# bottom_schem.net
KiCad netlist of a schematic drawn in Altium Designer
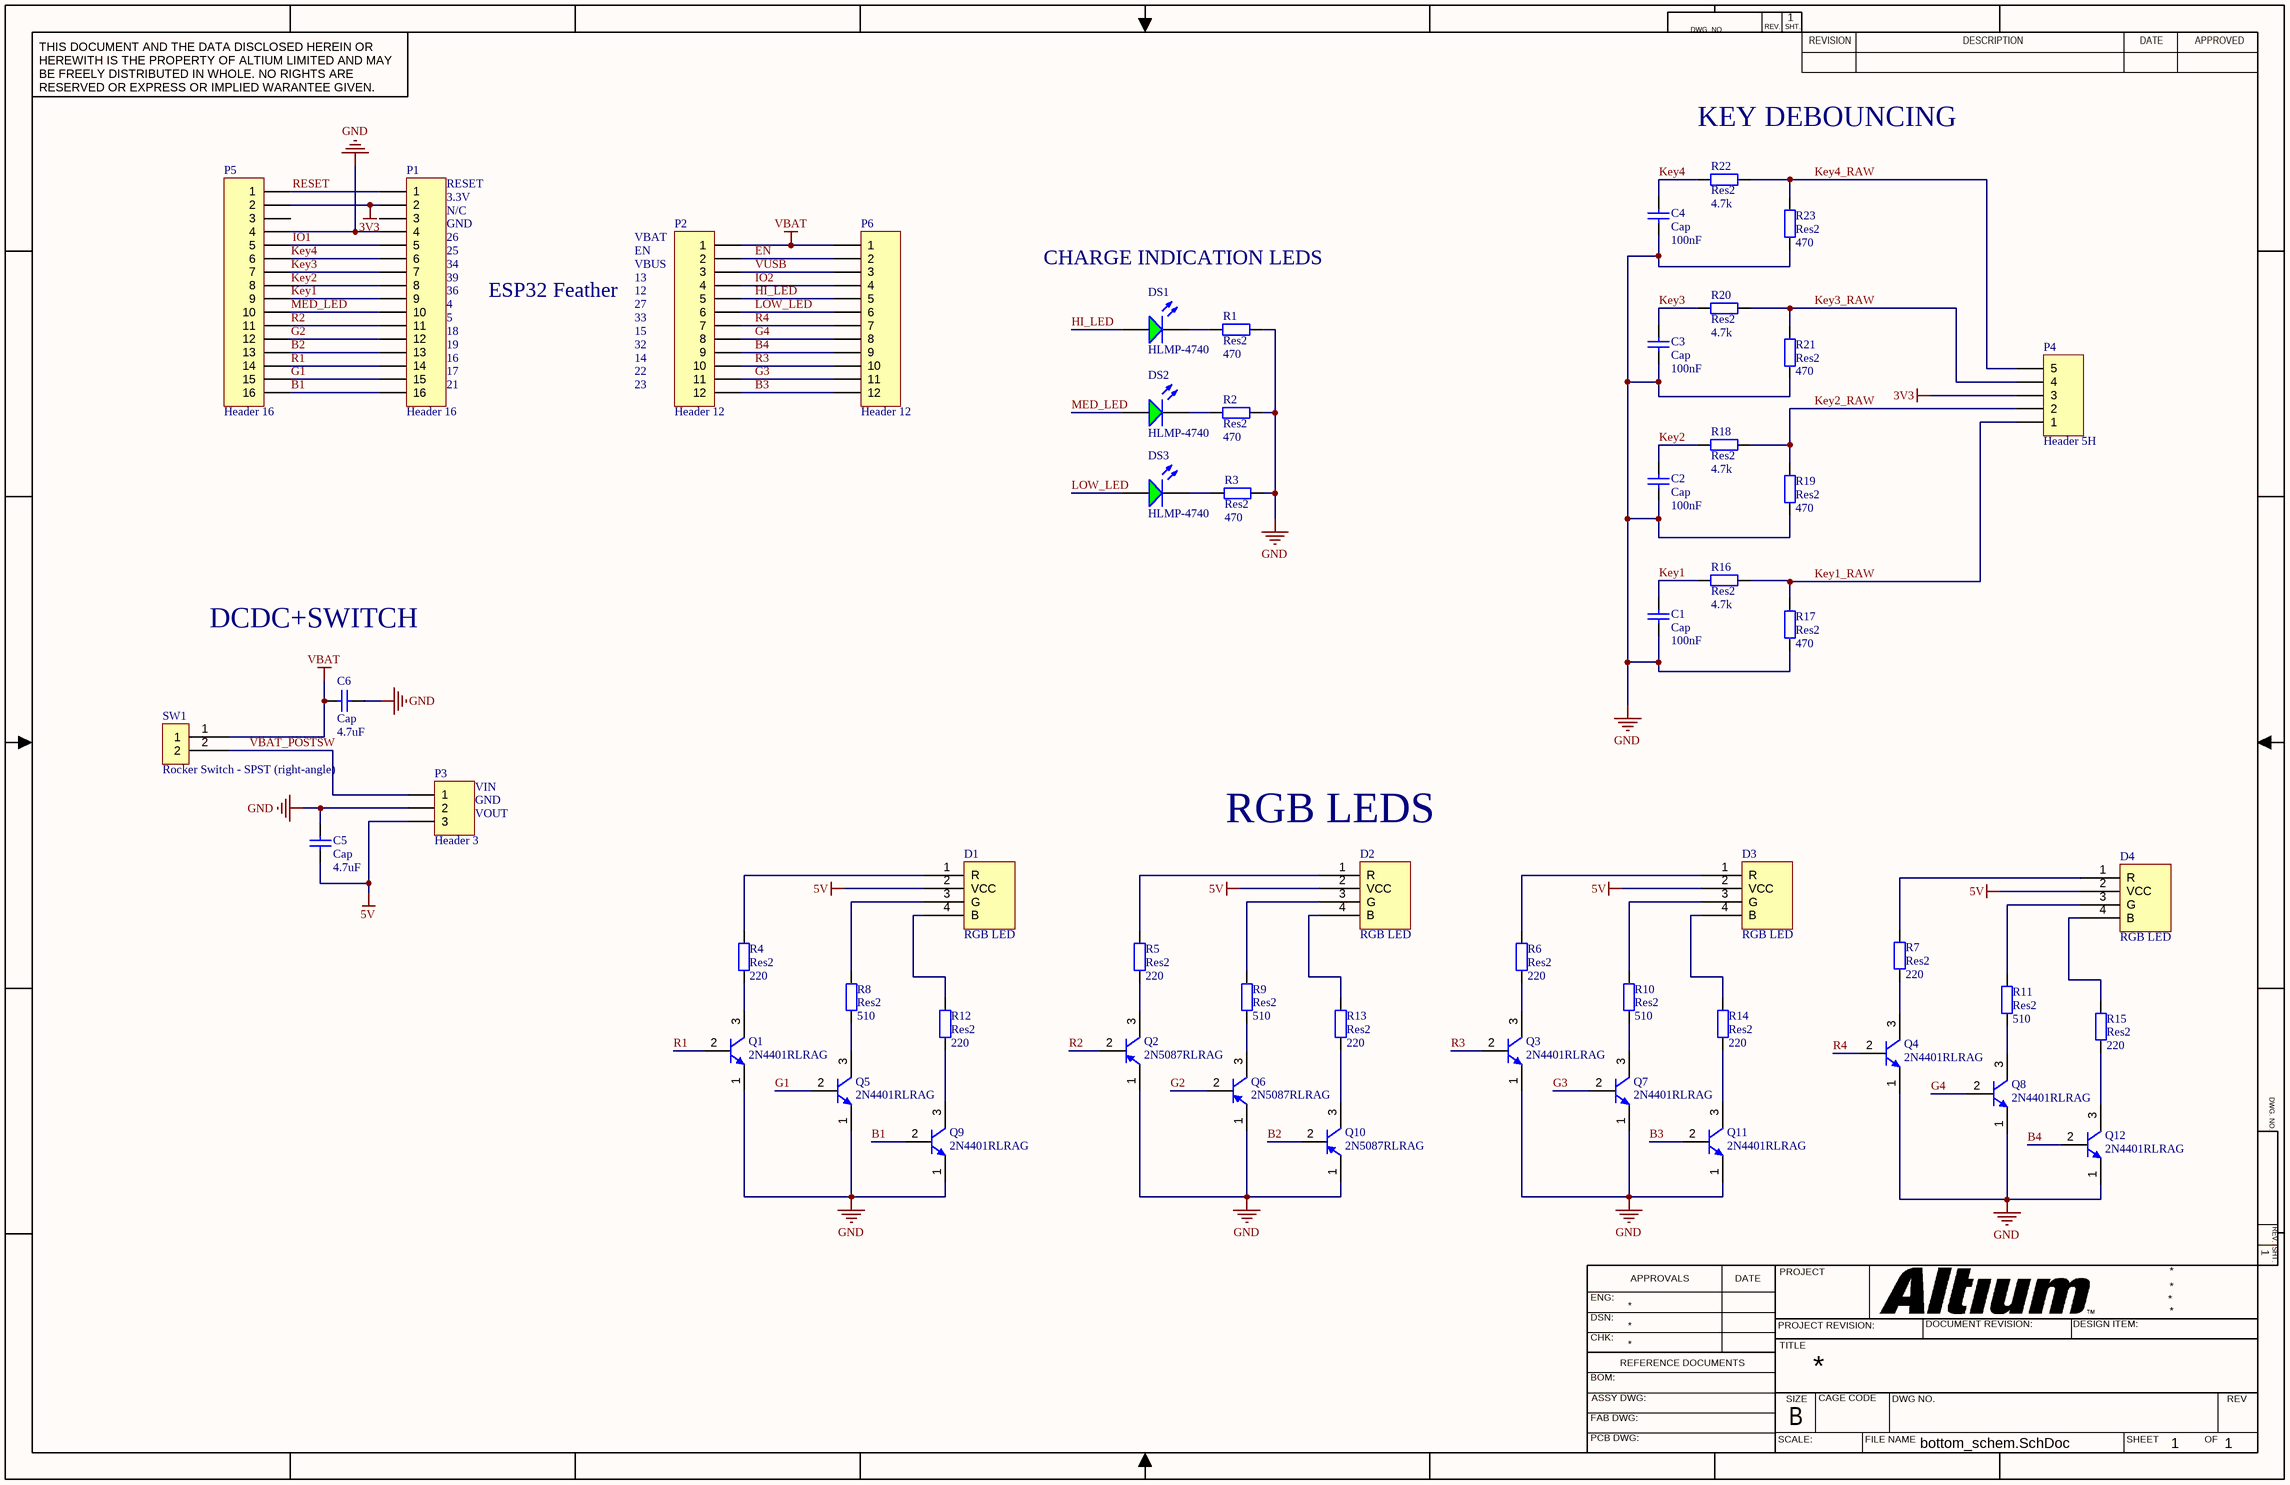
[diagram p0: bottom_schem.SchDoc]

(export (version "E")
  (design (tool "Eeschema 10.0.6"))
  (components
    (comp (ref "C1")
      (value "Cap")
      (footprint "RAD-0.3")
      (description "Capacitor")
      (fields (field (name "ALTIUM_VALUE") "100nF") (field (name "PUBLISHER") "Altium Limited"))
      (libsource (lib "Miscellaneous Devices") (part "Cap"))
    )
    (comp (ref "C2")
      (value "Cap")
      (footprint "RAD-0.3")
      (description "Capacitor")
      (fields (field (name "ALTIUM_VALUE") "100nF") (field (name "PUBLISHER") "Altium Limited"))
      (libsource (lib "Miscellaneous Devices") (part "Cap"))
    )
    (comp (ref "C3")
      (value "Cap")
      (footprint "RAD-0.3")
      (description "Capacitor")
      (fields (field (name "ALTIUM_VALUE") "100nF") (field (name "PUBLISHER") "Altium Limited"))
      (libsource (lib "Miscellaneous Devices") (part "Cap"))
    )
    (comp (ref "C4")
      (value "Cap")
      (footprint "RAD-0.3")
      (description "Capacitor")
      (fields (field (name "ALTIUM_VALUE") "100nF") (field (name "PUBLISHER") "Altium Limited"))
      (libsource (lib "Miscellaneous Devices") (part "Cap"))
    )
    (comp (ref "C5")
      (value "Cap")
      (footprint "RAD-0.3")
      (description "Capacitor")
      (fields (field (name "ALTIUM_VALUE") "4.7uF") (field (name "PUBLISHER") "Altium Limited"))
      (libsource (lib "Miscellaneous Devices") (part "Cap"))
    )
    (comp (ref "C6")
      (value "Cap")
      (footprint "RAD-0.3")
      (description "Capacitor")
      (fields (field (name "ALTIUM_VALUE") "4.7uF") (field (name "PUBLISHER") "Altium Limited"))
      (libsource (lib "Miscellaneous Devices") (part "Cap"))
    )
    (comp (ref "D1")
      (value "RGB LED")
      (footprint "New footprint 1")
      (description "4-pin common anode RGB LED")
      (libsource (lib "RGB LED") (part "CMP-007-00036-1"))
    )
    (comp (ref "D2")
      (value "RGB LED")
      (footprint "New footprint 1")
      (description "4-pin common anode RGB LED")
      (libsource (lib "RGB LED") (part "CMP-007-00036-1"))
    )
    (comp (ref "D3")
      (value "RGB LED")
      (footprint "New footprint 1")
      (description "4-pin common anode RGB LED")
      (libsource (lib "RGB LED") (part "CMP-007-00036-1"))
    )
    (comp (ref "D4")
      (value "RGB LED")
      (footprint "New footprint 1")
      (description "4-pin common anode RGB LED")
      (libsource (lib "RGB LED") (part "CMP-007-00036-1"))
    )
    (comp (ref "DS1")
      (value "HLMP-4740")
      (footprint "AVAG-HLMP-4740")
      (description "T-1 3/4 (5 mm) Low Current LED Lamp, Green, 1.9 V, -20 to 100 degC, 2-Pin THD, RoHS, Bulk")
      (fields (field (name "MANUFACTURER") "AvagoTechnologies"))
      (libsource (lib "Altium Content Vault") (part "LED-GREEN-AK-2"))
    )
    (comp (ref "DS2")
      (value "HLMP-4740")
      (footprint "AVAG-HLMP-4740")
      (description "T-1 3/4 (5 mm) Low Current LED Lamp, Green, 1.9 V, -20 to 100 degC, 2-Pin THD, RoHS, Bulk")
      (fields (field (name "MANUFACTURER") "AvagoTechnologies"))
      (libsource (lib "Altium Content Vault") (part "LED-GREEN-AK-2"))
    )
    (comp (ref "DS3")
      (value "HLMP-4740")
      (footprint "AVAG-HLMP-4740")
      (description "T-1 3/4 (5 mm) Low Current LED Lamp, Green, 1.9 V, -20 to 100 degC, 2-Pin THD, RoHS, Bulk")
      (fields (field (name "MANUFACTURER") "AvagoTechnologies"))
      (libsource (lib "Altium Content Vault") (part "LED-GREEN-AK-2"))
    )
    (comp (ref "P1")
      (value "Header 16")
      (footprint "HDR1X16")
      (description "Header, 16-Pin")
      (fields (field (name "PUBLISHER") "Altium Limited"))
      (libsource (lib "") (part "Header 16_1"))
    )
    (comp (ref "P2")
      (value "Header 12")
      (footprint "HDR1X12")
      (description "Header, 12-Pin")
      (fields (field (name "PUBLISHER") "Altium Limited"))
      (libsource (lib "") (part "Header 12_1"))
    )
    (comp (ref "P3")
      (value "Header 3")
      (footprint "HDR1X3")
      (description "Header, 3-Pin")
      (fields (field (name "PUBLISHER") "Altium Limited"))
      (libsource (lib "Miscellaneous Connectors") (part "Header 3"))
    )
    (comp (ref "P4")
      (value "Header 5H")
      (footprint "HDR1X5H")
      (description "Header, 5-Pin, Right Angle")
      (fields (field (name "PUBLISHER") "Altium Limited"))
      (libsource (lib "Miscellaneous Connectors") (part "Header 5H"))
    )
    (comp (ref "P5")
      (value "Header 16")
      (footprint "HDR1X16")
      (description "Header, 16-Pin")
      (fields (field (name "PUBLISHER") "Altium Limited"))
      (libsource (lib "Miscellaneous Connectors") (part "Header 16"))
    )
    (comp (ref "P6")
      (value "Header 12")
      (footprint "HDR1X12")
      (description "Header, 12-Pin")
      (fields (field (name "PUBLISHER") "Altium Limited"))
      (libsource (lib "Miscellaneous Connectors") (part "Header 12"))
    )
    (comp (ref "Q1")
      (value "2N4401RLRAG")
      (footprint "ONSC-TO-92-3-29-11_AM_BL")
      (description "General Purpose Transistor, NPN Silicon, 3-Pin TO-92, Pb-Free, Tape and Reel")
      (fields (field (name "MANUFACTURER") "On Semiconductor"))
      (libsource (lib "Altium Content Vault") (part "ONSC-NPN-E1B2C3-3"))
    )
    (comp (ref "Q2")
      (value "2N5087RLRAG")
      (footprint "ONSC-TO-92-3-29-11_AM_BL")
      (description "Amplifier Transistor, PNP Silicon, 3-Pin TO-92, Pb-Free, Tape and Reel")
      (fields (field (name "MANUFACTURER") "On Semiconductor"))
      (libsource (lib "Altium Content Vault") (part "ONSC-PNP-E1B2C3-3"))
    )
    (comp (ref "Q3")
      (value "2N4401RLRAG")
      (footprint "ONSC-TO-92-3-29-11_AM_BL")
      (description "General Purpose Transistor, NPN Silicon, 3-Pin TO-92, Pb-Free, Tape and Reel")
      (fields (field (name "MANUFACTURER") "On Semiconductor"))
      (libsource (lib "Altium Content Vault") (part "ONSC-NPN-E1B2C3-3"))
    )
    (comp (ref "Q4")
      (value "2N4401RLRAG")
      (footprint "ONSC-TO-92-3-29-11_AM_BL")
      (description "General Purpose Transistor, NPN Silicon, 3-Pin TO-92, Pb-Free, Tape and Reel")
      (fields (field (name "MANUFACTURER") "On Semiconductor"))
      (libsource (lib "Altium Content Vault") (part "ONSC-NPN-E1B2C3-3"))
    )
    (comp (ref "Q5")
      (value "2N4401RLRAG")
      (footprint "ONSC-TO-92-3-29-11_AM_BL")
      (description "General Purpose Transistor, NPN Silicon, 3-Pin TO-92, Pb-Free, Tape and Reel")
      (fields (field (name "MANUFACTURER") "On Semiconductor"))
      (libsource (lib "Altium Content Vault") (part "ONSC-NPN-E1B2C3-3"))
    )
    (comp (ref "Q6")
      (value "2N5087RLRAG")
      (footprint "ONSC-TO-92-3-29-11_AM_BL")
      (description "Amplifier Transistor, PNP Silicon, 3-Pin TO-92, Pb-Free, Tape and Reel")
      (fields (field (name "MANUFACTURER") "On Semiconductor"))
      (libsource (lib "Altium Content Vault") (part "ONSC-PNP-E1B2C3-3"))
    )
    (comp (ref "Q7")
      (value "2N4401RLRAG")
      (footprint "ONSC-TO-92-3-29-11_AM_BL")
      (description "General Purpose Transistor, NPN Silicon, 3-Pin TO-92, Pb-Free, Tape and Reel")
      (fields (field (name "MANUFACTURER") "On Semiconductor"))
      (libsource (lib "Altium Content Vault") (part "ONSC-NPN-E1B2C3-3"))
    )
    (comp (ref "Q8")
      (value "2N4401RLRAG")
      (footprint "ONSC-TO-92-3-29-11_AM_BL")
      (description "General Purpose Transistor, NPN Silicon, 3-Pin TO-92, Pb-Free, Tape and Reel")
      (fields (field (name "MANUFACTURER") "On Semiconductor"))
      (libsource (lib "Altium Content Vault") (part "ONSC-NPN-E1B2C3-3"))
    )
    (comp (ref "Q9")
      (value "2N4401RLRAG")
      (footprint "ONSC-TO-92-3-29-11_AM_BL")
      (description "General Purpose Transistor, NPN Silicon, 3-Pin TO-92, Pb-Free, Tape and Reel")
      (fields (field (name "MANUFACTURER") "On Semiconductor"))
      (libsource (lib "Altium Content Vault") (part "ONSC-NPN-E1B2C3-3"))
    )
    (comp (ref "Q10")
      (value "2N5087RLRAG")
      (footprint "ONSC-TO-92-3-29-11_AM_BL")
      (description "Amplifier Transistor, PNP Silicon, 3-Pin TO-92, Pb-Free, Tape and Reel")
      (fields (field (name "MANUFACTURER") "On Semiconductor"))
      (libsource (lib "Altium Content Vault") (part "ONSC-PNP-E1B2C3-3"))
    )
    (comp (ref "Q11")
      (value "2N4401RLRAG")
      (footprint "ONSC-TO-92-3-29-11_AM_BL")
      (description "General Purpose Transistor, NPN Silicon, 3-Pin TO-92, Pb-Free, Tape and Reel")
      (fields (field (name "MANUFACTURER") "On Semiconductor"))
      (libsource (lib "Altium Content Vault") (part "ONSC-NPN-E1B2C3-3"))
    )
    (comp (ref "Q12")
      (value "2N4401RLRAG")
      (footprint "ONSC-TO-92-3-29-11_AM_BL")
      (description "General Purpose Transistor, NPN Silicon, 3-Pin TO-92, Pb-Free, Tape and Reel")
      (fields (field (name "MANUFACTURER") "On Semiconductor"))
      (libsource (lib "Altium Content Vault") (part "ONSC-NPN-E1B2C3-3"))
    )
    (comp (ref "R1")
      (value "Res2")
      (footprint "AXIAL-0.4")
      (description "Resistor")
      (fields (field (name "ALTIUM_VALUE") "470") (field (name "PUBLISHER") "Altium Limited"))
      (libsource (lib "") (part "Res2_1"))
    )
    (comp (ref "R2")
      (value "Res2")
      (footprint "AXIAL-0.4")
      (description "Resistor")
      (fields (field (name "ALTIUM_VALUE") "470") (field (name "PUBLISHER") "Altium Limited"))
      (libsource (lib "") (part "Res2_1"))
    )
    (comp (ref "R3")
      (value "Res2")
      (footprint "AXIAL-0.4")
      (description "Resistor")
      (fields (field (name "ALTIUM_VALUE") "470") (field (name "PUBLISHER") "Altium Limited"))
      (libsource (lib "") (part "Res2_1"))
    )
    (comp (ref "R4")
      (value "Res2")
      (footprint "AXIAL-0.4")
      (description "Resistor")
      (fields (field (name "ALTIUM_VALUE") "220") (field (name "PUBLISHER") "Altium Limited"))
      (libsource (lib "Miscellaneous Devices") (part "Res2"))
    )
    (comp (ref "R5")
      (value "Res2")
      (footprint "AXIAL-0.4")
      (description "Resistor")
      (fields (field (name "ALTIUM_VALUE") "220") (field (name "PUBLISHER") "Altium Limited"))
      (libsource (lib "Miscellaneous Devices") (part "Res2"))
    )
    (comp (ref "R6")
      (value "Res2")
      (footprint "AXIAL-0.4")
      (description "Resistor")
      (fields (field (name "ALTIUM_VALUE") "220") (field (name "PUBLISHER") "Altium Limited"))
      (libsource (lib "Miscellaneous Devices") (part "Res2"))
    )
    (comp (ref "R7")
      (value "Res2")
      (footprint "AXIAL-0.4")
      (description "Resistor")
      (fields (field (name "ALTIUM_VALUE") "220") (field (name "PUBLISHER") "Altium Limited"))
      (libsource (lib "Miscellaneous Devices") (part "Res2"))
    )
    (comp (ref "R8")
      (value "Res2")
      (footprint "AXIAL-0.4")
      (description "Resistor")
      (fields (field (name "ALTIUM_VALUE") "510") (field (name "PUBLISHER") "Altium Limited"))
      (libsource (lib "Miscellaneous Devices") (part "Res2"))
    )
    (comp (ref "R9")
      (value "Res2")
      (footprint "AXIAL-0.4")
      (description "Resistor")
      (fields (field (name "ALTIUM_VALUE") "510") (field (name "PUBLISHER") "Altium Limited"))
      (libsource (lib "Miscellaneous Devices") (part "Res2"))
    )
    (comp (ref "R10")
      (value "Res2")
      (footprint "AXIAL-0.4")
      (description "Resistor")
      (fields (field (name "ALTIUM_VALUE") "510") (field (name "PUBLISHER") "Altium Limited"))
      (libsource (lib "Miscellaneous Devices") (part "Res2"))
    )
    (comp (ref "R11")
      (value "Res2")
      (footprint "AXIAL-0.4")
      (description "Resistor")
      (fields (field (name "ALTIUM_VALUE") "510") (field (name "PUBLISHER") "Altium Limited"))
      (libsource (lib "Miscellaneous Devices") (part "Res2"))
    )
    (comp (ref "R12")
      (value "Res2")
      (footprint "AXIAL-0.4")
      (description "Resistor")
      (fields (field (name "ALTIUM_VALUE") "220") (field (name "PUBLISHER") "Altium Limited"))
      (libsource (lib "Miscellaneous Devices") (part "Res2"))
    )
    (comp (ref "R13")
      (value "Res2")
      (footprint "AXIAL-0.4")
      (description "Resistor")
      (fields (field (name "ALTIUM_VALUE") "220") (field (name "PUBLISHER") "Altium Limited"))
      (libsource (lib "Miscellaneous Devices") (part "Res2"))
    )
    (comp (ref "R14")
      (value "Res2")
      (footprint "AXIAL-0.4")
      (description "Resistor")
      (fields (field (name "ALTIUM_VALUE") "220") (field (name "PUBLISHER") "Altium Limited"))
      (libsource (lib "Miscellaneous Devices") (part "Res2"))
    )
    (comp (ref "R15")
      (value "Res2")
      (footprint "AXIAL-0.4")
      (description "Resistor")
      (fields (field (name "ALTIUM_VALUE") "220") (field (name "PUBLISHER") "Altium Limited"))
      (libsource (lib "Miscellaneous Devices") (part "Res2"))
    )
    (comp (ref "R16")
      (value "Res2")
      (footprint "AXIAL-0.4")
      (description "Resistor")
      (fields (field (name "ALTIUM_VALUE") "4.7k") (field (name "PUBLISHER") "Altium Limited"))
      (libsource (lib "") (part "Res2_1"))
    )
    (comp (ref "R17")
      (value "Res2")
      (footprint "AXIAL-0.4")
      (description "Resistor")
      (fields (field (name "ALTIUM_VALUE") "470") (field (name "PUBLISHER") "Altium Limited"))
      (libsource (lib "Miscellaneous Devices") (part "Res2"))
    )
    (comp (ref "R18")
      (value "Res2")
      (footprint "AXIAL-0.4")
      (description "Resistor")
      (fields (field (name "ALTIUM_VALUE") "4.7k") (field (name "PUBLISHER") "Altium Limited"))
      (libsource (lib "") (part "Res2_1"))
    )
    (comp (ref "R19")
      (value "Res2")
      (footprint "AXIAL-0.4")
      (description "Resistor")
      (fields (field (name "ALTIUM_VALUE") "470") (field (name "PUBLISHER") "Altium Limited"))
      (libsource (lib "Miscellaneous Devices") (part "Res2"))
    )
    (comp (ref "R20")
      (value "Res2")
      (footprint "AXIAL-0.4")
      (description "Resistor")
      (fields (field (name "ALTIUM_VALUE") "4.7k") (field (name "PUBLISHER") "Altium Limited"))
      (libsource (lib "") (part "Res2_1"))
    )
    (comp (ref "R21")
      (value "Res2")
      (footprint "AXIAL-0.4")
      (description "Resistor")
      (fields (field (name "ALTIUM_VALUE") "470") (field (name "PUBLISHER") "Altium Limited"))
      (libsource (lib "Miscellaneous Devices") (part "Res2"))
    )
    (comp (ref "R22")
      (value "Res2")
      (footprint "AXIAL-0.4")
      (description "Resistor")
      (fields (field (name "ALTIUM_VALUE") "4.7k") (field (name "PUBLISHER") "Altium Limited"))
      (libsource (lib "") (part "Res2_1"))
    )
    (comp (ref "R23")
      (value "Res2")
      (footprint "AXIAL-0.4")
      (description "Resistor")
      (fields (field (name "ALTIUM_VALUE") "470") (field (name "PUBLISHER") "Altium Limited"))
      (libsource (lib "Miscellaneous Devices") (part "Res2"))
    )
    (comp (ref "SW1")
      (value "Rocker Switch - SPST (right-angle)")
      (footprint "Rocker Switch - SPST (right-angle)-Footprint-1")
      (description "Rated up to 15A @ 125V")
      (libsource (lib "Rocker_Switch") (part "CMP-011-00016-1"))
    )
  )
  (nets
    (net (code "1") (name "/B1") (class "Default")
      (node (ref "P1") (pin "16") (pinfunction "16_16") (pintype "passive"))
      (node (ref "P5") (pin "16") (pinfunction "16_16") (pintype "passive"))
      (node (ref "Q9") (pin "2") (pinfunction "B_2") (pintype "passive"))
    )
    (net (code "2") (name "/B2") (class "Default")
      (node (ref "P1") (pin "13") (pinfunction "13_13") (pintype "passive"))
      (node (ref "P5") (pin "13") (pinfunction "13_13") (pintype "passive"))
      (node (ref "Q10") (pin "2") (pinfunction "B_2") (pintype "passive"))
    )
    (net (code "3") (name "/B3") (class "Default")
      (node (ref "P2") (pin "12") (pinfunction "12_12") (pintype "passive"))
      (node (ref "P6") (pin "12") (pinfunction "12_12") (pintype "passive"))
      (node (ref "Q11") (pin "2") (pinfunction "B_2") (pintype "passive"))
    )
    (net (code "4") (name "/B4") (class "Default")
      (node (ref "P2") (pin "9") (pinfunction "9_9") (pintype "passive"))
      (node (ref "P6") (pin "9") (pinfunction "9_9") (pintype "passive"))
      (node (ref "Q12") (pin "2") (pinfunction "B_2") (pintype "passive"))
    )
    (net (code "5") (name "/EN") (class "Default")
      (node (ref "P2") (pin "2") (pinfunction "2_2") (pintype "passive"))
      (node (ref "P6") (pin "2") (pinfunction "2_2") (pintype "passive"))
    )
    (net (code "6") (name "/G1") (class "Default")
      (node (ref "P1") (pin "15") (pinfunction "15_15") (pintype "passive"))
      (node (ref "P5") (pin "15") (pinfunction "15_15") (pintype "passive"))
      (node (ref "Q5") (pin "2") (pinfunction "B_2") (pintype "passive"))
    )
    (net (code "7") (name "/G2") (class "Default")
      (node (ref "P1") (pin "12") (pinfunction "12_12") (pintype "passive"))
      (node (ref "P5") (pin "12") (pinfunction "12_12") (pintype "passive"))
      (node (ref "Q6") (pin "2") (pinfunction "B_2") (pintype "passive"))
    )
    (net (code "8") (name "/G3") (class "Default")
      (node (ref "P2") (pin "11") (pinfunction "11_11") (pintype "passive"))
      (node (ref "P6") (pin "11") (pinfunction "11_11") (pintype "passive"))
      (node (ref "Q7") (pin "2") (pinfunction "B_2") (pintype "passive"))
    )
    (net (code "9") (name "/G4") (class "Default")
      (node (ref "P2") (pin "8") (pinfunction "8_8") (pintype "passive"))
      (node (ref "P6") (pin "8") (pinfunction "8_8") (pintype "passive"))
      (node (ref "Q8") (pin "2") (pinfunction "B_2") (pintype "passive"))
    )
    (net (code "10") (name "/HI_LED") (class "Default")
      (node (ref "DS1") (pin "1") (pinfunction "A_1") (pintype "passive"))
      (node (ref "P2") (pin "5") (pinfunction "5_5") (pintype "passive"))
      (node (ref "P6") (pin "5") (pinfunction "5_5") (pintype "passive"))
    )
    (net (code "11") (name "/IO1") (class "Default")
      (node (ref "P1") (pin "5") (pinfunction "5_5") (pintype "passive"))
      (node (ref "P5") (pin "5") (pinfunction "5_5") (pintype "passive"))
    )
    (net (code "12") (name "/IO2") (class "Default")
      (node (ref "P2") (pin "4") (pinfunction "4_4") (pintype "passive"))
      (node (ref "P6") (pin "4") (pinfunction "4_4") (pintype "passive"))
    )
    (net (code "13") (name "/Key1") (class "Default")
      (node (ref "C1") (pin "1") (pinfunction "1_1") (pintype "passive"))
      (node (ref "P1") (pin "9") (pinfunction "9_9") (pintype "passive"))
      (node (ref "P5") (pin "9") (pinfunction "9_9") (pintype "passive"))
      (node (ref "R16") (pin "2") (pinfunction "2_2") (pintype "passive"))
    )
    (net (code "14") (name "/Key1_RAW") (class "Default")
      (node (ref "P4") (pin "1") (pinfunction "1_1") (pintype "passive"))
      (node (ref "R16") (pin "1") (pinfunction "1_1") (pintype "passive"))
      (node (ref "R17") (pin "2") (pinfunction "2_2") (pintype "passive"))
    )
    (net (code "15") (name "/Key2") (class "Default")
      (node (ref "C2") (pin "1") (pinfunction "1_1") (pintype "passive"))
      (node (ref "P1") (pin "8") (pinfunction "8_8") (pintype "passive"))
      (node (ref "P5") (pin "8") (pinfunction "8_8") (pintype "passive"))
      (node (ref "R18") (pin "2") (pinfunction "2_2") (pintype "passive"))
    )
    (net (code "16") (name "/Key2_RAW") (class "Default")
      (node (ref "P4") (pin "2") (pinfunction "2_2") (pintype "passive"))
      (node (ref "R18") (pin "1") (pinfunction "1_1") (pintype "passive"))
      (node (ref "R19") (pin "2") (pinfunction "2_2") (pintype "passive"))
    )
    (net (code "17") (name "/Key3") (class "Default")
      (node (ref "C3") (pin "1") (pinfunction "1_1") (pintype "passive"))
      (node (ref "P1") (pin "7") (pinfunction "7_7") (pintype "passive"))
      (node (ref "P5") (pin "7") (pinfunction "7_7") (pintype "passive"))
      (node (ref "R20") (pin "2") (pinfunction "2_2") (pintype "passive"))
    )
    (net (code "18") (name "/Key3_RAW") (class "Default")
      (node (ref "P4") (pin "4") (pinfunction "4_4") (pintype "passive"))
      (node (ref "R20") (pin "1") (pinfunction "1_1") (pintype "passive"))
      (node (ref "R21") (pin "2") (pinfunction "2_2") (pintype "passive"))
    )
    (net (code "19") (name "/Key4") (class "Default")
      (node (ref "C4") (pin "1") (pinfunction "1_1") (pintype "passive"))
      (node (ref "P1") (pin "6") (pinfunction "6_6") (pintype "passive"))
      (node (ref "P5") (pin "6") (pinfunction "6_6") (pintype "passive"))
      (node (ref "R22") (pin "2") (pinfunction "2_2") (pintype "passive"))
    )
    (net (code "20") (name "/Key4_RAW") (class "Default")
      (node (ref "P4") (pin "5") (pinfunction "5_5") (pintype "passive"))
      (node (ref "R22") (pin "1") (pinfunction "1_1") (pintype "passive"))
      (node (ref "R23") (pin "2") (pinfunction "2_2") (pintype "passive"))
    )
    (net (code "21") (name "/LOW_LED") (class "Default")
      (node (ref "DS3") (pin "1") (pinfunction "A_1") (pintype "passive"))
      (node (ref "P2") (pin "6") (pinfunction "6_6") (pintype "passive"))
      (node (ref "P6") (pin "6") (pinfunction "6_6") (pintype "passive"))
    )
    (net (code "22") (name "/MED_LED") (class "Default")
      (node (ref "DS2") (pin "1") (pinfunction "A_1") (pintype "passive"))
      (node (ref "P1") (pin "10") (pinfunction "10_10") (pintype "passive"))
      (node (ref "P5") (pin "10") (pinfunction "10_10") (pintype "passive"))
    )
    (net (code "23") (name "/R1") (class "Default")
      (node (ref "P1") (pin "14") (pinfunction "14_14") (pintype "passive"))
      (node (ref "P5") (pin "14") (pinfunction "14_14") (pintype "passive"))
      (node (ref "Q1") (pin "2") (pinfunction "B_2") (pintype "passive"))
    )
    (net (code "24") (name "/R2") (class "Default")
      (node (ref "P1") (pin "11") (pinfunction "11_11") (pintype "passive"))
      (node (ref "P5") (pin "11") (pinfunction "11_11") (pintype "passive"))
      (node (ref "Q2") (pin "2") (pinfunction "B_2") (pintype "passive"))
    )
    (net (code "25") (name "/R3") (class "Default")
      (node (ref "P2") (pin "10") (pinfunction "10_10") (pintype "passive"))
      (node (ref "P6") (pin "10") (pinfunction "10_10") (pintype "passive"))
      (node (ref "Q3") (pin "2") (pinfunction "B_2") (pintype "passive"))
    )
    (net (code "26") (name "/R4") (class "Default")
      (node (ref "P2") (pin "7") (pinfunction "7_7") (pintype "passive"))
      (node (ref "P6") (pin "7") (pinfunction "7_7") (pintype "passive"))
      (node (ref "Q4") (pin "2") (pinfunction "B_2") (pintype "passive"))
    )
    (net (code "27") (name "/RESET") (class "Default")
      (node (ref "P1") (pin "1") (pinfunction "1_1") (pintype "passive"))
      (node (ref "P5") (pin "1") (pinfunction "1_1") (pintype "passive"))
    )
    (net (code "28") (name "/VBAT_POSTSW") (class "Default")
      (node (ref "P3") (pin "1") (pinfunction "1_1") (pintype "passive"))
      (node (ref "SW1") (pin "2") (pinfunction "2_2") (pintype "passive"))
    )
    (net (code "29") (name "/VUSB") (class "Default")
      (node (ref "P2") (pin "3") (pinfunction "3_3") (pintype "passive"))
      (node (ref "P6") (pin "3") (pinfunction "3_3") (pintype "passive"))
    )
    (net (code "30") (name "3V3") (class "Default")
      (node (ref "P1") (pin "2") (pinfunction "2_2") (pintype "passive"))
      (node (ref "P4") (pin "3") (pinfunction "3_3") (pintype "passive"))
      (node (ref "P5") (pin "2") (pinfunction "2_2") (pintype "passive"))
    )
    (net (code "31") (name "5V") (class "Default")
      (node (ref "C5") (pin "2") (pinfunction "2_2") (pintype "passive"))
      (node (ref "D1") (pin "2") (pinfunction "VCC_2") (pintype "passive"))
      (node (ref "D2") (pin "2") (pinfunction "VCC_2") (pintype "passive"))
      (node (ref "D3") (pin "2") (pinfunction "VCC_2") (pintype "passive"))
      (node (ref "D4") (pin "2") (pinfunction "VCC_2") (pintype "passive"))
      (node (ref "P3") (pin "3") (pinfunction "3_3") (pintype "passive"))
    )
    (net (code "32") (name "GND") (class "Default")
      (node (ref "C1") (pin "2") (pinfunction "2_2") (pintype "passive"))
      (node (ref "C2") (pin "2") (pinfunction "2_2") (pintype "passive"))
      (node (ref "C3") (pin "2") (pinfunction "2_2") (pintype "passive"))
      (node (ref "C4") (pin "2") (pinfunction "2_2") (pintype "passive"))
      (node (ref "C5") (pin "1") (pinfunction "1_1") (pintype "passive"))
      (node (ref "C6") (pin "2") (pinfunction "2_2") (pintype "passive"))
      (node (ref "P1") (pin "4") (pinfunction "4_4") (pintype "passive"))
      (node (ref "P3") (pin "2") (pinfunction "2_2") (pintype "passive"))
      (node (ref "P5") (pin "4") (pinfunction "4_4") (pintype "passive"))
      (node (ref "Q1") (pin "1") (pinfunction "E_1") (pintype "passive"))
      (node (ref "Q10") (pin "1") (pinfunction "E_1") (pintype "passive"))
      (node (ref "Q11") (pin "1") (pinfunction "E_1") (pintype "passive"))
      (node (ref "Q12") (pin "1") (pinfunction "E_1") (pintype "passive"))
      (node (ref "Q2") (pin "1") (pinfunction "E_1") (pintype "passive"))
      (node (ref "Q3") (pin "1") (pinfunction "E_1") (pintype "passive"))
      (node (ref "Q4") (pin "1") (pinfunction "E_1") (pintype "passive"))
      (node (ref "Q5") (pin "1") (pinfunction "E_1") (pintype "passive"))
      (node (ref "Q6") (pin "1") (pinfunction "E_1") (pintype "passive"))
      (node (ref "Q7") (pin "1") (pinfunction "E_1") (pintype "passive"))
      (node (ref "Q8") (pin "1") (pinfunction "E_1") (pintype "passive"))
      (node (ref "Q9") (pin "1") (pinfunction "E_1") (pintype "passive"))
      (node (ref "R1") (pin "1") (pinfunction "1_1") (pintype "passive"))
      (node (ref "R17") (pin "1") (pinfunction "1_1") (pintype "passive"))
      (node (ref "R19") (pin "1") (pinfunction "1_1") (pintype "passive"))
      (node (ref "R2") (pin "1") (pinfunction "1_1") (pintype "passive"))
      (node (ref "R21") (pin "1") (pinfunction "1_1") (pintype "passive"))
      (node (ref "R23") (pin "1") (pinfunction "1_1") (pintype "passive"))
      (node (ref "R3") (pin "1") (pinfunction "1_1") (pintype "passive"))
    )
    (net (code "33") (name "Net-(D1-B)") (class "Default")
      (node (ref "D1") (pin "4") (pinfunction "B_4") (pintype "passive"))
      (node (ref "R12") (pin "2") (pinfunction "2_2") (pintype "passive"))
    )
    (net (code "34") (name "Net-(D1-G)") (class "Default")
      (node (ref "D1") (pin "3") (pinfunction "G_3") (pintype "passive"))
      (node (ref "R8") (pin "2") (pinfunction "2_2") (pintype "passive"))
    )
    (net (code "35") (name "Net-(D1-R)") (class "Default")
      (node (ref "D1") (pin "1") (pinfunction "R_1") (pintype "passive"))
      (node (ref "R4") (pin "2") (pinfunction "2_2") (pintype "passive"))
    )
    (net (code "36") (name "Net-(D2-B)") (class "Default")
      (node (ref "D2") (pin "4") (pinfunction "B_4") (pintype "passive"))
      (node (ref "R13") (pin "2") (pinfunction "2_2") (pintype "passive"))
    )
    (net (code "37") (name "Net-(D2-G)") (class "Default")
      (node (ref "D2") (pin "3") (pinfunction "G_3") (pintype "passive"))
      (node (ref "R9") (pin "2") (pinfunction "2_2") (pintype "passive"))
    )
    (net (code "38") (name "Net-(D2-R)") (class "Default")
      (node (ref "D2") (pin "1") (pinfunction "R_1") (pintype "passive"))
      (node (ref "R5") (pin "2") (pinfunction "2_2") (pintype "passive"))
    )
    (net (code "39") (name "Net-(D3-B)") (class "Default")
      (node (ref "D3") (pin "4") (pinfunction "B_4") (pintype "passive"))
      (node (ref "R14") (pin "2") (pinfunction "2_2") (pintype "passive"))
    )
    (net (code "40") (name "Net-(D3-G)") (class "Default")
      (node (ref "D3") (pin "3") (pinfunction "G_3") (pintype "passive"))
      (node (ref "R10") (pin "2") (pinfunction "2_2") (pintype "passive"))
    )
    (net (code "41") (name "Net-(D3-R)") (class "Default")
      (node (ref "D3") (pin "1") (pinfunction "R_1") (pintype "passive"))
      (node (ref "R6") (pin "2") (pinfunction "2_2") (pintype "passive"))
    )
    (net (code "42") (name "Net-(D4-B)") (class "Default")
      (node (ref "D4") (pin "4") (pinfunction "B_4") (pintype "passive"))
      (node (ref "R15") (pin "2") (pinfunction "2_2") (pintype "passive"))
    )
    (net (code "43") (name "Net-(D4-G)") (class "Default")
      (node (ref "D4") (pin "3") (pinfunction "G_3") (pintype "passive"))
      (node (ref "R11") (pin "2") (pinfunction "2_2") (pintype "passive"))
    )
    (net (code "44") (name "Net-(D4-R)") (class "Default")
      (node (ref "D4") (pin "1") (pinfunction "R_1") (pintype "passive"))
      (node (ref "R7") (pin "2") (pinfunction "2_2") (pintype "passive"))
    )
    (net (code "45") (name "Net-(DS1-K)") (class "Default")
      (node (ref "DS1") (pin "2") (pinfunction "K_2") (pintype "passive"))
      (node (ref "R1") (pin "2") (pinfunction "2_2") (pintype "passive"))
    )
    (net (code "46") (name "Net-(DS2-K)") (class "Default")
      (node (ref "DS2") (pin "2") (pinfunction "K_2") (pintype "passive"))
      (node (ref "R2") (pin "2") (pinfunction "2_2") (pintype "passive"))
    )
    (net (code "47") (name "Net-(DS3-K)") (class "Default")
      (node (ref "DS3") (pin "2") (pinfunction "K_2") (pintype "passive"))
      (node (ref "R3") (pin "2") (pinfunction "2_2") (pintype "passive"))
    )
    (net (code "48") (name "Net-(Q1-C)") (class "Default")
      (node (ref "Q1") (pin "3") (pinfunction "C_3") (pintype "passive"))
      (node (ref "R4") (pin "1") (pinfunction "1_1") (pintype "passive"))
    )
    (net (code "49") (name "Net-(Q2-C)") (class "Default")
      (node (ref "Q2") (pin "3") (pinfunction "C_3") (pintype "passive"))
      (node (ref "R5") (pin "1") (pinfunction "1_1") (pintype "passive"))
    )
    (net (code "50") (name "Net-(Q3-C)") (class "Default")
      (node (ref "Q3") (pin "3") (pinfunction "C_3") (pintype "passive"))
      (node (ref "R6") (pin "1") (pinfunction "1_1") (pintype "passive"))
    )
    (net (code "51") (name "Net-(Q4-C)") (class "Default")
      (node (ref "Q4") (pin "3") (pinfunction "C_3") (pintype "passive"))
      (node (ref "R7") (pin "1") (pinfunction "1_1") (pintype "passive"))
    )
    (net (code "52") (name "Net-(Q5-C)") (class "Default")
      (node (ref "Q5") (pin "3") (pinfunction "C_3") (pintype "passive"))
      (node (ref "R8") (pin "1") (pinfunction "1_1") (pintype "passive"))
    )
    (net (code "53") (name "Net-(Q6-C)") (class "Default")
      (node (ref "Q6") (pin "3") (pinfunction "C_3") (pintype "passive"))
      (node (ref "R9") (pin "1") (pinfunction "1_1") (pintype "passive"))
    )
    (net (code "54") (name "Net-(Q7-C)") (class "Default")
      (node (ref "Q7") (pin "3") (pinfunction "C_3") (pintype "passive"))
      (node (ref "R10") (pin "1") (pinfunction "1_1") (pintype "passive"))
    )
    (net (code "55") (name "Net-(Q8-C)") (class "Default")
      (node (ref "Q8") (pin "3") (pinfunction "C_3") (pintype "passive"))
      (node (ref "R11") (pin "1") (pinfunction "1_1") (pintype "passive"))
    )
    (net (code "56") (name "Net-(Q9-C)") (class "Default")
      (node (ref "Q9") (pin "3") (pinfunction "C_3") (pintype "passive"))
      (node (ref "R12") (pin "1") (pinfunction "1_1") (pintype "passive"))
    )
    (net (code "57") (name "Net-(Q10-C)") (class "Default")
      (node (ref "Q10") (pin "3") (pinfunction "C_3") (pintype "passive"))
      (node (ref "R13") (pin "1") (pinfunction "1_1") (pintype "passive"))
    )
    (net (code "58") (name "Net-(Q11-C)") (class "Default")
      (node (ref "Q11") (pin "3") (pinfunction "C_3") (pintype "passive"))
      (node (ref "R14") (pin "1") (pinfunction "1_1") (pintype "passive"))
    )
    (net (code "59") (name "Net-(Q12-C)") (class "Default")
      (node (ref "Q12") (pin "3") (pinfunction "C_3") (pintype "passive"))
      (node (ref "R15") (pin "1") (pinfunction "1_1") (pintype "passive"))
    )
    (net (code "60") (name "VBAT") (class "Default")
      (node (ref "C6") (pin "1") (pinfunction "1_1") (pintype "passive"))
      (node (ref "P2") (pin "1") (pinfunction "1_1") (pintype "passive"))
      (node (ref "P6") (pin "1") (pinfunction "1_1") (pintype "passive"))
      (node (ref "SW1") (pin "1") (pinfunction "1_1") (pintype "passive"))
    )
    (net (code "61") (name "unconnected-(P1-Pad3)") (class "Default")
      (node (ref "P1") (pin "3") (pinfunction "3_3") (pintype "passive"))
    )
    (net (code "62") (name "unconnected-(P5-Pad3)") (class "Default")
      (node (ref "P5") (pin "3") (pinfunction "3_3") (pintype "passive"))
    )
  )
)
